# Mother_board_main.net
KiCad netlist of a schematic drawn in Altium Designer
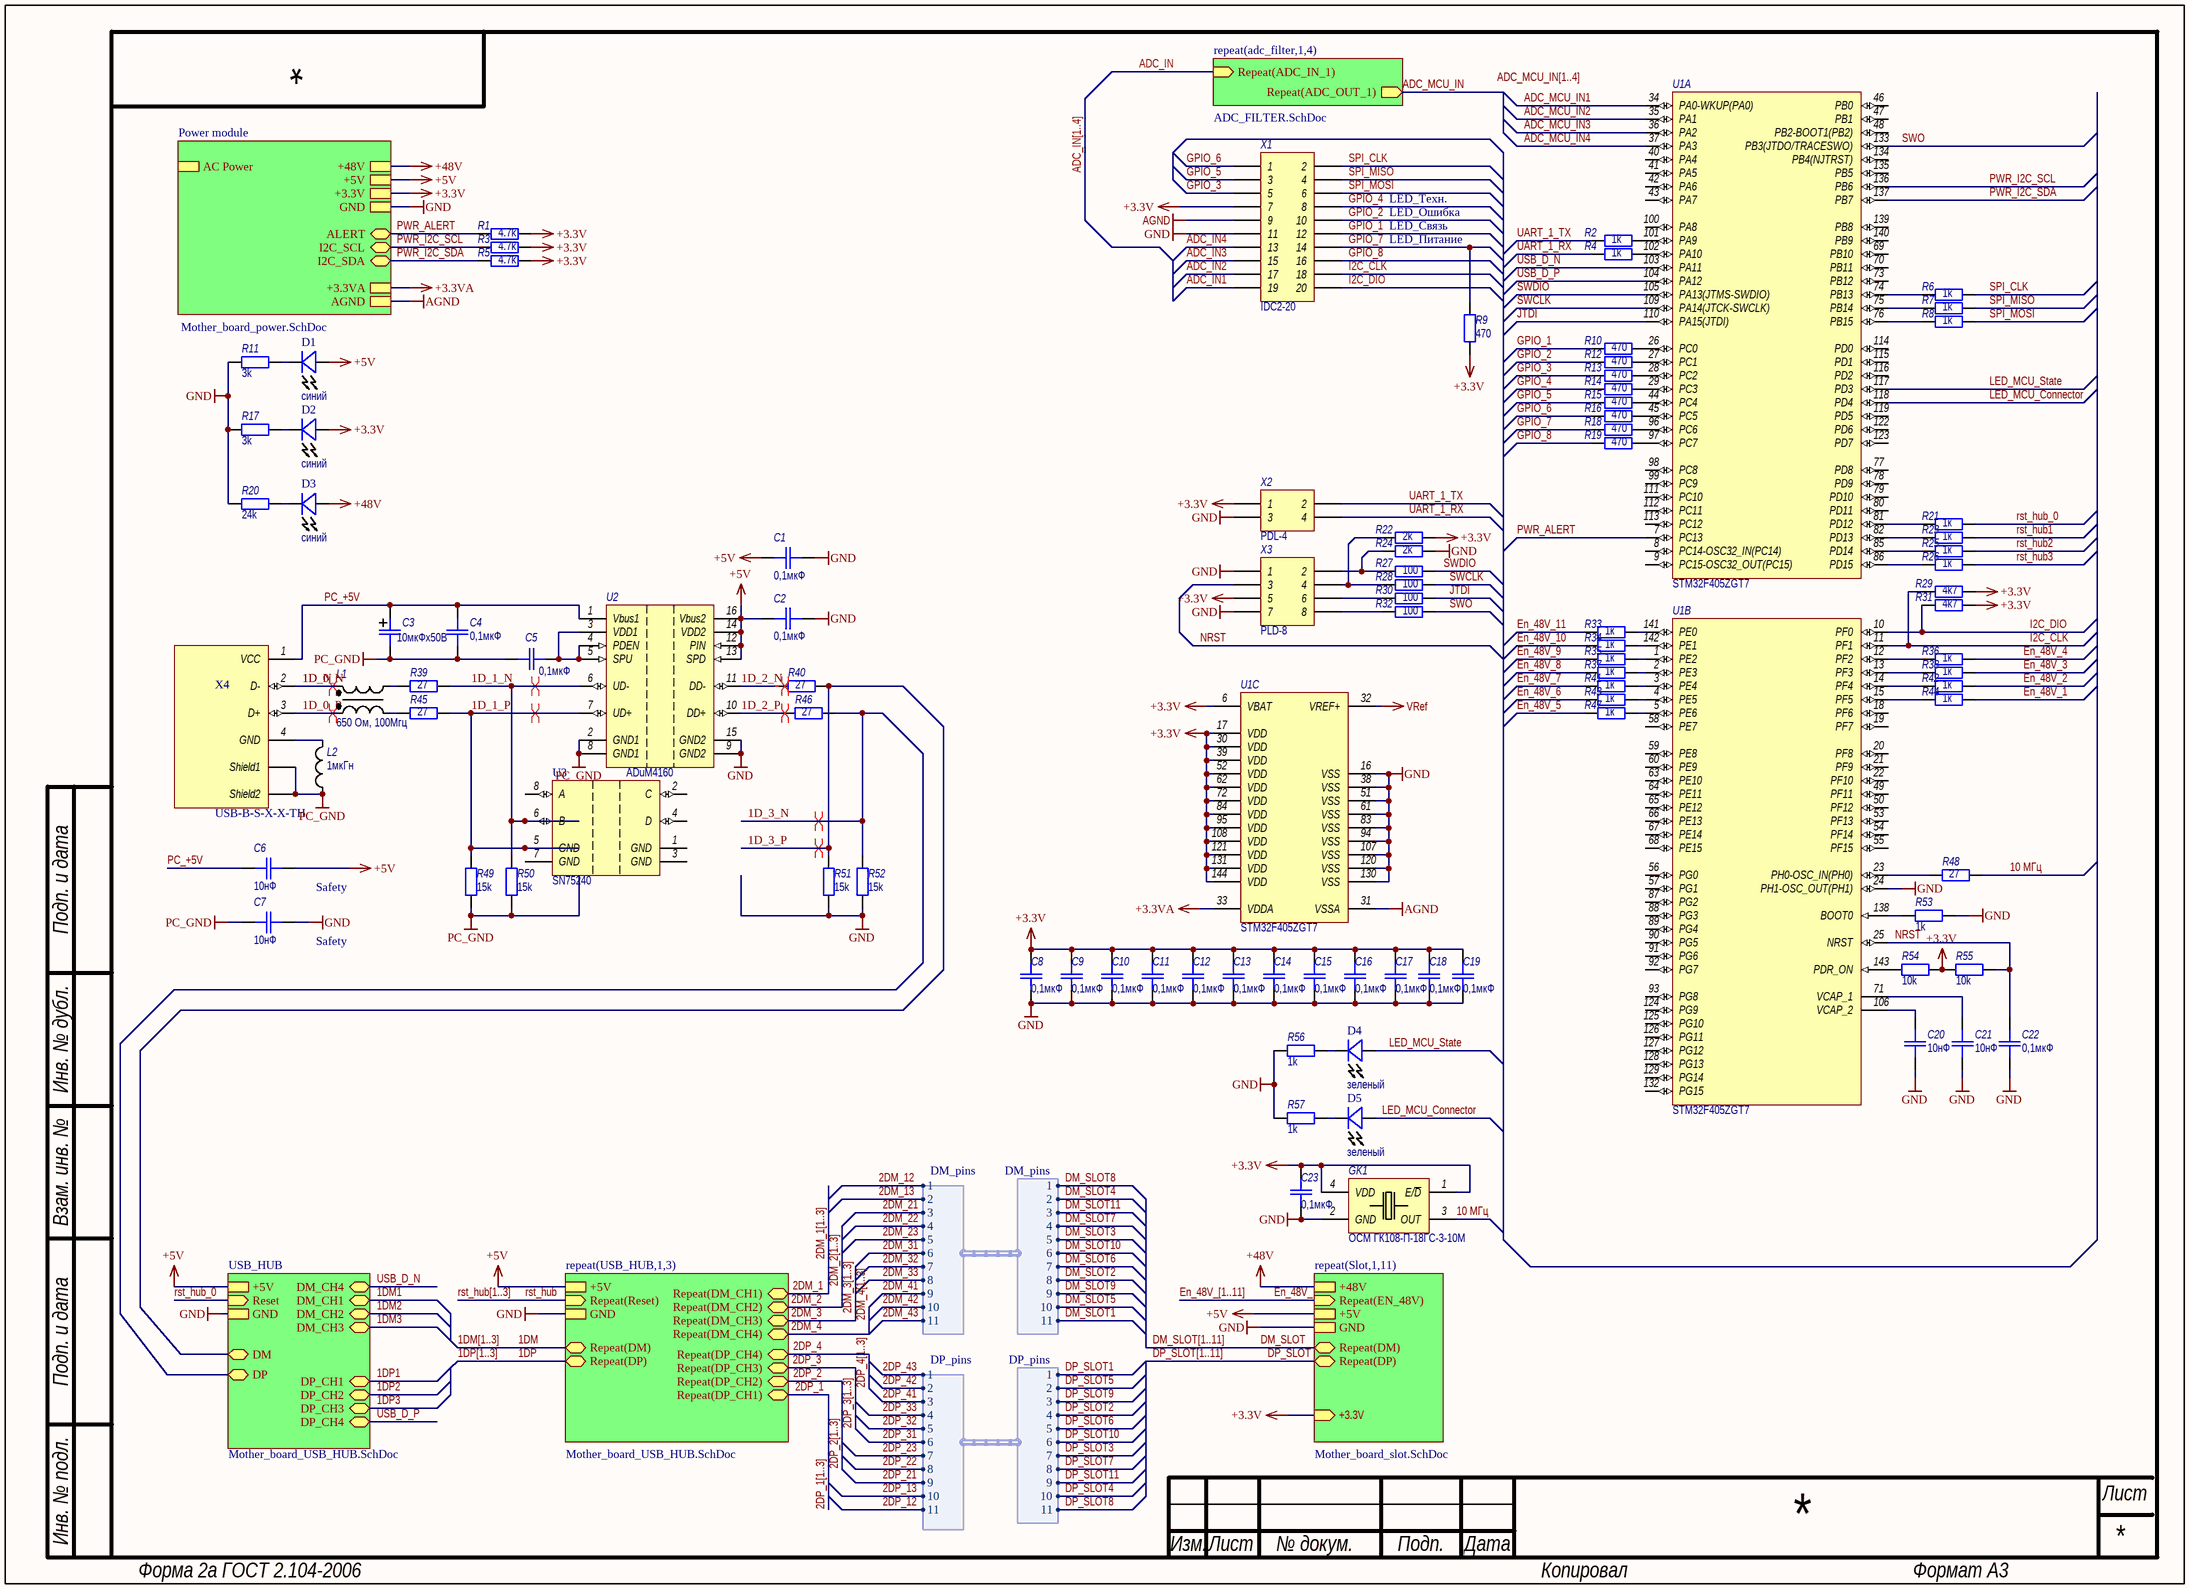
[diagram p0: Mother_board_main.SchDoc]

(export (version "E")
  (design (tool "Eeschema 10.0.6"))
  (components
    (comp (ref "C1")
      (value "0,1мкФ")
      (footprint "SMD_0805")
      (description "Capacitor")
      (libsource (lib "Passive") (part "Capacitor"))
    )
    (comp (ref "C2")
      (value "0,1мкФ")
      (footprint "SMD_0805")
      (description "Capacitor")
      (libsource (lib "Passive") (part "Capacitor"))
    )
    (comp (ref "C3")
      (value "10мкФх50В")
      (footprint "SMD_size_B")
      (description "Polarized capacitor")
      (libsource (lib "Passive") (part "Capacitor_pol"))
    )
    (comp (ref "C4")
      (value "0,1мкФ")
      (footprint "SMD_0805")
      (description "Capacitor")
      (libsource (lib "Passive") (part "Capacitor"))
    )
    (comp (ref "C5")
      (value "0,1мкФ")
      (footprint "SMD_0805")
      (description "Capacitor")
      (libsource (lib "Passive") (part "Capacitor"))
    )
    (comp (ref "C6")
      (value "10нФ")
      (footprint "SMD_0805")
      (description "Capacitor")
      (libsource (lib "Passive") (part "Capacitor"))
    )
    (comp (ref "C7")
      (value "10нФ")
      (footprint "SMD_0805")
      (description "Capacitor")
      (libsource (lib "Passive") (part "Capacitor"))
    )
    (comp (ref "C8")
      (value "0,1мкФ")
      (footprint "SMD_0805")
      (description "Capacitor")
      (libsource (lib "Passive") (part "Capacitor"))
    )
    (comp (ref "C9")
      (value "0,1мкФ")
      (footprint "SMD_0805")
      (description "Capacitor")
      (libsource (lib "Passive") (part "Capacitor"))
    )
    (comp (ref "C10")
      (value "0,1мкФ")
      (footprint "SMD_0805")
      (description "Capacitor")
      (libsource (lib "Passive") (part "Capacitor"))
    )
    (comp (ref "C11")
      (value "0,1мкФ")
      (footprint "SMD_0805")
      (description "Capacitor")
      (libsource (lib "Passive") (part "Capacitor"))
    )
    (comp (ref "C12")
      (value "0,1мкФ")
      (footprint "SMD_0805")
      (description "Capacitor")
      (libsource (lib "Passive") (part "Capacitor"))
    )
    (comp (ref "C13")
      (value "0,1мкФ")
      (footprint "SMD_0805")
      (description "Capacitor")
      (libsource (lib "Passive") (part "Capacitor"))
    )
    (comp (ref "C14")
      (value "0,1мкФ")
      (footprint "SMD_0805")
      (description "Capacitor")
      (libsource (lib "Passive") (part "Capacitor"))
    )
    (comp (ref "C15")
      (value "0,1мкФ")
      (footprint "SMD_0805")
      (description "Capacitor")
      (libsource (lib "Passive") (part "Capacitor"))
    )
    (comp (ref "C16")
      (value "0,1мкФ")
      (footprint "SMD_0805")
      (description "Capacitor")
      (libsource (lib "Passive") (part "Capacitor"))
    )
    (comp (ref "C17")
      (value "0,1мкФ")
      (footprint "SMD_0805")
      (description "Capacitor")
      (libsource (lib "Passive") (part "Capacitor"))
    )
    (comp (ref "C18")
      (value "0,1мкФ")
      (footprint "SMD_0805")
      (description "Capacitor")
      (libsource (lib "Passive") (part "Capacitor"))
    )
    (comp (ref "C19")
      (value "0,1мкФ")
      (footprint "SMD_0805")
      (description "Capacitor")
      (libsource (lib "Passive") (part "Capacitor"))
    )
    (comp (ref "C20")
      (value "10нФ")
      (footprint "SMD_0805")
      (description "Capacitor")
      (libsource (lib "Passive") (part "Capacitor"))
    )
    (comp (ref "C21")
      (value "10нФ")
      (footprint "SMD_0805")
      (description "Capacitor")
      (libsource (lib "Passive") (part "Capacitor"))
    )
    (comp (ref "C22")
      (value "0,1мкФ")
      (footprint "SMD_0805")
      (description "Capacitor")
      (libsource (lib "Passive") (part "Capacitor"))
    )
    (comp (ref "C23")
      (value "0,1мкФ")
      (footprint "SMD_0805")
      (description "Capacitor")
      (libsource (lib "Passive") (part "Capacitor"))
    )
    (comp (ref "D1")
      (value "синий")
      (footprint "LED-0805")
      (fields (field (name "Comment") "LED"))
      (libsource (lib "*") (part "LED"))
    )
    (comp (ref "D2")
      (value "синий")
      (footprint "LED-0805")
      (fields (field (name "Comment") "LED"))
      (libsource (lib "*") (part "LED"))
    )
    (comp (ref "D3")
      (value "синий")
      (footprint "LED-0805")
      (fields (field (name "Comment") "LED"))
      (libsource (lib "*") (part "LED"))
    )
    (comp (ref "D4")
      (value "зеленый")
      (footprint "LED-0805+circle")
      (fields (field (name "Comment") "LED"))
      (libsource (lib "Diod") (part "LED"))
    )
    (comp (ref "D5")
      (value "зеленый")
      (footprint "LED-0805+circle")
      (fields (field (name "Comment") "LED"))
      (libsource (lib "Diod") (part "LED"))
    )
    (comp (ref "GK1")
      (value "GK108-P")
      (footprint "SMD_7050_Crystal_Oscillator")
      (description "Crystall oscillator, CMOS, 3.3V, SMD7050")
      (fields (field (name "НАИМЕНОВАНИЕ") "ОСМ ГК108-П-18ГС-3-10М"))
      (libsource (lib "Oscillator") (part "Crystal_Oscillator"))
    )
    (comp (ref "L1")
      (value "650 Ом, 100Мгц")
      (footprint "ACM2012")
      (description "Coupled inductor")
      (libsource (lib "Passive") (part "Inductor_coupled"))
    )
    (comp (ref "L2")
      (value "1мкГн")
      (footprint "SMD_0805")
      (description "Inductor")
      (libsource (lib "Passive") (part "Inductor"))
    )
    (comp (ref "R1")
      (value "4.7k")
      (footprint "SMD_0805")
      (description "Resistor")
      (libsource (lib "*") (part "Resistor"))
    )
    (comp (ref "R2")
      (value "1k")
      (footprint "SMD_0805")
      (description "Resistor")
      (libsource (lib "") (part "Resistor_2"))
    )
    (comp (ref "R3")
      (value "4.7k")
      (footprint "SMD_0805")
      (description "Resistor")
      (libsource (lib "*") (part "Resistor"))
    )
    (comp (ref "R4")
      (value "1k")
      (footprint "SMD_0805")
      (description "Resistor")
      (libsource (lib "") (part "Resistor_2"))
    )
    (comp (ref "R5")
      (value "4.7k")
      (footprint "SMD_0805")
      (description "Resistor")
      (libsource (lib "*") (part "Resistor"))
    )
    (comp (ref "R6")
      (value "1k")
      (footprint "SMD_0805")
      (description "Resistor")
      (libsource (lib "") (part "Resistor_2"))
    )
    (comp (ref "R7")
      (value "1k")
      (footprint "SMD_0805")
      (description "Resistor")
      (libsource (lib "") (part "Resistor_2"))
    )
    (comp (ref "R8")
      (value "1k")
      (footprint "SMD_0805")
      (description "Resistor")
      (libsource (lib "") (part "Resistor_2"))
    )
    (comp (ref "R9")
      (value "470")
      (footprint "SMD_0805")
      (description "Resistor")
      (libsource (lib "") (part "Resistor_1"))
    )
    (comp (ref "R10")
      (value "470")
      (footprint "SMD_0805")
      (description "Resistor")
      (libsource (lib "") (part "Resistor_2"))
    )
    (comp (ref "R11")
      (value "3k")
      (footprint "SMD_0805")
      (description "Resistor")
      (libsource (lib "") (part "Resistor_2"))
    )
    (comp (ref "R12")
      (value "470")
      (footprint "SMD_0805")
      (description "Resistor")
      (libsource (lib "") (part "Resistor_2"))
    )
    (comp (ref "R13")
      (value "470")
      (footprint "SMD_0805")
      (description "Resistor")
      (libsource (lib "") (part "Resistor_2"))
    )
    (comp (ref "R14")
      (value "470")
      (footprint "SMD_0805")
      (description "Resistor")
      (libsource (lib "") (part "Resistor_2"))
    )
    (comp (ref "R15")
      (value "470")
      (footprint "SMD_0805")
      (description "Resistor")
      (libsource (lib "") (part "Resistor_2"))
    )
    (comp (ref "R16")
      (value "470")
      (footprint "SMD_0805")
      (description "Resistor")
      (libsource (lib "") (part "Resistor_2"))
    )
    (comp (ref "R17")
      (value "3k")
      (footprint "SMD_0805")
      (description "Resistor")
      (libsource (lib "") (part "Resistor_2"))
    )
    (comp (ref "R18")
      (value "470")
      (footprint "SMD_0805")
      (description "Resistor")
      (libsource (lib "") (part "Resistor_2"))
    )
    (comp (ref "R19")
      (value "470")
      (footprint "SMD_0805")
      (description "Resistor")
      (libsource (lib "") (part "Resistor_2"))
    )
    (comp (ref "R20")
      (value "24k")
      (footprint "SMD_0805")
      (description "Resistor")
      (libsource (lib "") (part "Resistor_2"))
    )
    (comp (ref "R21")
      (value "1к")
      (footprint "SMD_0805")
      (description "Resistor")
      (libsource (lib "Passive") (part "Resistor"))
    )
    (comp (ref "R22")
      (value "2k")
      (footprint "SMD_0805")
      (description "Resistor")
      (libsource (lib "") (part "Resistor_2"))
    )
    (comp (ref "R23")
      (value "1к")
      (footprint "SMD_0805")
      (description "Resistor")
      (libsource (lib "Passive") (part "Resistor"))
    )
    (comp (ref "R24")
      (value "2k")
      (footprint "SMD_0805")
      (description "Resistor")
      (libsource (lib "") (part "Resistor_2"))
    )
    (comp (ref "R25")
      (value "1к")
      (footprint "SMD_0805")
      (description "Resistor")
      (libsource (lib "Passive") (part "Resistor"))
    )
    (comp (ref "R26")
      (value "1к")
      (footprint "SMD_0805")
      (description "Resistor")
      (libsource (lib "Passive") (part "Resistor"))
    )
    (comp (ref "R27")
      (value "100")
      (footprint "SMD_0805")
      (description "Resistor")
      (libsource (lib "") (part "Resistor_2"))
    )
    (comp (ref "R28")
      (value "100")
      (footprint "SMD_0805")
      (description "Resistor")
      (libsource (lib "") (part "Resistor_2"))
    )
    (comp (ref "R29")
      (value "4k7")
      (footprint "SMD_0805")
      (description "Resistor")
      (libsource (lib "") (part "Resistor_2"))
    )
    (comp (ref "R30")
      (value "100")
      (footprint "SMD_0805")
      (description "Resistor")
      (libsource (lib "") (part "Resistor_2"))
    )
    (comp (ref "R31")
      (value "4k7")
      (footprint "SMD_0805")
      (description "Resistor")
      (libsource (lib "") (part "Resistor_2"))
    )
    (comp (ref "R32")
      (value "100")
      (footprint "SMD_0805")
      (description "Resistor")
      (libsource (lib "") (part "Resistor_2"))
    )
    (comp (ref "R33")
      (value "1к")
      (footprint "SMD_0805")
      (description "Resistor")
      (libsource (lib "Passive") (part "Resistor"))
    )
    (comp (ref "R34")
      (value "1к")
      (footprint "SMD_0805")
      (description "Resistor")
      (libsource (lib "Passive") (part "Resistor"))
    )
    (comp (ref "R35")
      (value "1к")
      (footprint "SMD_0805")
      (description "Resistor")
      (libsource (lib "Passive") (part "Resistor"))
    )
    (comp (ref "R36")
      (value "1к")
      (footprint "SMD_0805")
      (description "Resistor")
      (libsource (lib "Passive") (part "Resistor"))
    )
    (comp (ref "R37")
      (value "1к")
      (footprint "SMD_0805")
      (description "Resistor")
      (libsource (lib "Passive") (part "Resistor"))
    )
    (comp (ref "R38")
      (value "1к")
      (footprint "SMD_0805")
      (description "Resistor")
      (libsource (lib "Passive") (part "Resistor"))
    )
    (comp (ref "R39")
      (value "27")
      (footprint "SMD_0805")
      (description "Resistor")
      (libsource (lib "") (part "Resistor_1"))
    )
    (comp (ref "R40")
      (value "27")
      (footprint "SMD_0805")
      (description "Resistor")
      (libsource (lib "") (part "Resistor_1"))
    )
    (comp (ref "R41")
      (value "1к")
      (footprint "SMD_0805")
      (description "Resistor")
      (libsource (lib "Passive") (part "Resistor"))
    )
    (comp (ref "R42")
      (value "1к")
      (footprint "SMD_0805")
      (description "Resistor")
      (libsource (lib "Passive") (part "Resistor"))
    )
    (comp (ref "R43")
      (value "1к")
      (footprint "SMD_0805")
      (description "Resistor")
      (libsource (lib "Passive") (part "Resistor"))
    )
    (comp (ref "R44")
      (value "1к")
      (footprint "SMD_0805")
      (description "Resistor")
      (libsource (lib "Passive") (part "Resistor"))
    )
    (comp (ref "R45")
      (value "27")
      (footprint "SMD_0805")
      (description "Resistor")
      (libsource (lib "") (part "Resistor_1"))
    )
    (comp (ref "R46")
      (value "27")
      (footprint "SMD_0805")
      (description "Resistor")
      (libsource (lib "") (part "Resistor_1"))
    )
    (comp (ref "R47")
      (value "1к")
      (footprint "SMD_0805")
      (description "Resistor")
      (libsource (lib "Passive") (part "Resistor"))
    )
    (comp (ref "R48")
      (value "27")
      (footprint "SMD_0805")
      (description "Resistor")
      (libsource (lib "Passive") (part "Resistor"))
    )
    (comp (ref "R49")
      (value "15k")
      (footprint "SMD_0805")
      (description "Resistor")
      (libsource (lib "") (part "Resistor_3"))
    )
    (comp (ref "R50")
      (value "15k")
      (footprint "SMD_0805")
      (description "Resistor")
      (libsource (lib "") (part "Resistor_3"))
    )
    (comp (ref "R51")
      (value "15k")
      (footprint "SMD_0805")
      (description "Resistor")
      (libsource (lib "") (part "Resistor_2"))
    )
    (comp (ref "R52")
      (value "15k")
      (footprint "SMD_0805")
      (description "Resistor")
      (libsource (lib "") (part "Resistor_2"))
    )
    (comp (ref "R53")
      (value "1k")
      (footprint "SMD_0805")
      (description "Resistor")
      (libsource (lib "Passive") (part "Resistor"))
    )
    (comp (ref "R54")
      (value "10k")
      (footprint "SMD_0805")
      (description "Resistor")
      (libsource (lib "Passive") (part "Resistor"))
    )
    (comp (ref "R55")
      (value "10k")
      (footprint "SMD_0805")
      (description "Resistor")
      (libsource (lib "Passive") (part "Resistor"))
    )
    (comp (ref "R56")
      (value "1k")
      (footprint "SMD_0805")
      (description "Resistor")
      (libsource (lib "") (part "Resistor_2"))
    )
    (comp (ref "R57")
      (value "1k")
      (footprint "SMD_0805")
      (description "Resistor")
      (libsource (lib "") (part "Resistor_2"))
    )
    (comp (ref "U1")
      (value "STM32F405ZGT7")
      (footprint "LQFP144")
      (fields (field (name "НАИМЕНОВАНИЕ") "STM32F405ZGT7"))
      (libsource (lib "MCU") (part "STM32F405ZGT"))
    )
    (comp (ref "U2")
      (value "ADuM1402")
      (footprint "SOIC-16-WIDE")
      (description "Quad Channel Digital Isolator, 2.5 KV rms Insulation Rating")
      (fields (field (name "НАИМЕНОВАНИЕ") "ADuM4160"))
      (libsource (lib "Isolator") (part "ADuM4160"))
    )
    (comp (ref "U3")
      (value "SN75240")
      (footprint "SN75240")
      (description "ESD-защита")
      (fields (field (name "НАИМЕНОВАНИЕ") "SN75240"))
      (libsource (lib "SN75240") (part "SN75240"))
    )
    (comp (ref "X1")
      (value "Header 2X20")
      (footprint "PLD2-20")
      (description "Header, 20-Pin, Dual row")
      (fields (field (name "НАИМЕНОВАНИЕ") "IDC2-20"))
      (libsource (lib "Connector") (part "Header 2X20"))
    )
    (comp (ref "X2")
      (value "Header 2X4")
      (footprint "PBD-4")
      (description "Header, 4-Pin, Dual row")
      (fields (field (name "НАИМЕНОВАНИЕ") "PDL-4"))
      (libsource (lib "Connector") (part "Header 2X4"))
    )
    (comp (ref "X3")
      (value "Header 2X8")
      (footprint "PBD-8")
      (description "Header, 8-Pin, Dual row")
      (fields (field (name "НАИМЕНОВАНИЕ") "PLD-8"))
      (libsource (lib "Connector") (part "Header 2X8"))
    )
    (comp (ref "X4")
      (value "USB-B-S-X-X-TH")
      (footprint "*SAMTEC_USB-B-S-X-X-TH_USB-B-S-X-X-TH(Primary)")
      (description "USB-B (USB TYPE-B) USB 2.0 Receptacle Connector 4 Position Through Hole, Right Angle")
      (fields
        (field (name "BUYPART") "https://www.snapeda.com/parts/USB-B-S-F-B-TH/Samtec%20Inc./view-part/226211/?ref=eda")
        (field (name "MP") "USB-B-S-F-B-TH")
      )
      (libsource (lib "USB-B-S-X-X-TH") (part "USB-B-S-X-X-TH"))
    )
  )
  (nets
    (net (code "5") (name "+3.3V") (class "Default")
      (node (ref "C10") (pin "2") (pinfunction "2_2") (pintype "passive"))
      (node (ref "C11") (pin "2") (pinfunction "2_2") (pintype "passive"))
      (node (ref "C12") (pin "2") (pinfunction "2_2") (pintype "passive"))
      (node (ref "C13") (pin "2") (pinfunction "2_2") (pintype "passive"))
      (node (ref "C14") (pin "2") (pinfunction "2_2") (pintype "passive"))
      (node (ref "C15") (pin "2") (pinfunction "2_2") (pintype "passive"))
      (node (ref "C16") (pin "2") (pinfunction "2_2") (pintype "passive"))
      (node (ref "C17") (pin "2") (pinfunction "2_2") (pintype "passive"))
      (node (ref "C18") (pin "2") (pinfunction "2_2") (pintype "passive"))
      (node (ref "C19") (pin "2") (pinfunction "2_2") (pintype "passive"))
      (node (ref "C23") (pin "2") (pinfunction "2_2") (pintype "passive"))
      (node (ref "C8") (pin "2") (pinfunction "2_2") (pintype "passive"))
      (node (ref "C9") (pin "2") (pinfunction "2_2") (pintype "passive"))
      (node (ref "D2") (pin "1") (pinfunction "A_1") (pintype "passive"))
      (node (ref "GK1") (pin "1") (pinfunction "E/~{D}_1") (pintype "passive"))
      (node (ref "GK1") (pin "4") (pinfunction "VDD_4") (pintype "passive"))
      (node (ref "R1") (pin "1") (pinfunction "1_1") (pintype "passive"))
      (node (ref "R22") (pin "2") (pinfunction "2_2") (pintype "passive"))
      (node (ref "R29") (pin "2") (pinfunction "2_2") (pintype "passive"))
      (node (ref "R3") (pin "1") (pinfunction "1_1") (pintype "passive"))
      (node (ref "R31") (pin "2") (pinfunction "2_2") (pintype "passive"))
      (node (ref "R5") (pin "1") (pinfunction "1_1") (pintype "passive"))
      (node (ref "R54") (pin "1") (pinfunction "1_1") (pintype "passive"))
      (node (ref "R55") (pin "2") (pinfunction "2_2") (pintype "passive"))
      (node (ref "R9") (pin "1") (pinfunction "1_1") (pintype "passive"))
      (node (ref "U1") (pin "108") (pinfunction "VDD_108") (pintype "power_in"))
      (node (ref "U1") (pin "121") (pinfunction "VDD_121") (pintype "power_in"))
      (node (ref "U1") (pin "131") (pinfunction "VDD_131") (pintype "power_in"))
      (node (ref "U1") (pin "144") (pinfunction "VDD_144") (pintype "power_in"))
      (node (ref "U1") (pin "17") (pinfunction "VDD_17") (pintype "power_in"))
      (node (ref "U1") (pin "30") (pinfunction "VDD_30") (pintype "power_in"))
      (node (ref "U1") (pin "39") (pinfunction "VDD_39") (pintype "power_in"))
      (node (ref "U1") (pin "52") (pinfunction "VDD_52") (pintype "power_in"))
      (node (ref "U1") (pin "6") (pinfunction "VBAT_6") (pintype "power_in"))
      (node (ref "U1") (pin "62") (pinfunction "VDD_62") (pintype "power_in"))
      (node (ref "U1") (pin "72") (pinfunction "VDD_72") (pintype "power_in"))
      (node (ref "U1") (pin "84") (pinfunction "VDD_84") (pintype "power_in"))
      (node (ref "U1") (pin "95") (pinfunction "VDD_95") (pintype "power_in"))
      (node (ref "X1") (pin "7") (pinfunction "7_7") (pintype "passive"))
      (node (ref "X2") (pin "1") (pinfunction "1_1") (pintype "passive"))
      (node (ref "X3") (pin "5") (pinfunction "5_5") (pintype "passive"))
    )
    (net (code "6") (name "+3.3VA") (class "Default")
      (node (ref "U1") (pin "33") (pinfunction "VDDA_33") (pintype "power_in"))
    )
    (net (code "7") (name "+5V") (class "Default")
      (node (ref "C1") (pin "2") (pinfunction "2_2") (pintype "passive"))
      (node (ref "C2") (pin "2") (pinfunction "2_2") (pintype "passive"))
      (node (ref "C6") (pin "2") (pinfunction "2_2") (pintype "passive"))
      (node (ref "D1") (pin "1") (pinfunction "A_1") (pintype "passive"))
      (node (ref "U2") (pin "12") (pinfunction "PIN_12") (pintype "input"))
      (node (ref "U2") (pin "13") (pinfunction "SPD_13") (pintype "input"))
      (node (ref "U2") (pin "14") (pinfunction "VDD2_14") (pintype "power_in"))
      (node (ref "U2") (pin "16") (pinfunction "Vbus2_16") (pintype "power_in"))
    )
    (net (code "8") (name "+48V") (class "Default")
      (node (ref "D3") (pin "1") (pinfunction "A_1") (pintype "passive"))
    )
    (net (code "19") (name "/1D_0_N") (class "Default")
      (node (ref "L1") (pin "2") (pinfunction "2_2") (pintype "passive"))
      (node (ref "X4") (pin "2") (pinfunction "D-_2") (pintype "bidirectional"))
    )
    (net (code "20") (name "/1D_0_P") (class "Default")
      (node (ref "L1") (pin "3") (pinfunction "3_3") (pintype "passive"))
      (node (ref "X4") (pin "3") (pinfunction "D+_3") (pintype "bidirectional"))
    )
    (net (code "21") (name "/1D_1_N") (class "Default")
      (node (ref "R39") (pin "2") (pinfunction "2_2") (pintype "passive"))
      (node (ref "R50") (pin "2") (pinfunction "2_2") (pintype "passive"))
      (node (ref "U2") (pin "6") (pinfunction "UD-_6") (pintype "bidirectional"))
      (node (ref "U3") (pin "6") (pinfunction "B_6") (pintype "bidirectional"))
    )
    (net (code "22") (name "/1D_1_P") (class "Default")
      (node (ref "R45") (pin "2") (pinfunction "2_2") (pintype "passive"))
      (node (ref "R49") (pin "2") (pinfunction "2_2") (pintype "passive"))
      (node (ref "U2") (pin "7") (pinfunction "UD+_7") (pintype "bidirectional"))
      (node (ref "U3") (pin "5") (pinfunction "GND_5") (pintype "power_in"))
    )
    (net (code "23") (name "/1D_2_N") (class "Default")
      (node (ref "R40") (pin "1") (pinfunction "1_1") (pintype "passive"))
      (node (ref "U2") (pin "11") (pinfunction "DD-_11") (pintype "bidirectional"))
    )
    (net (code "24") (name "/1D_2_P") (class "Default")
      (node (ref "R46") (pin "1") (pinfunction "1_1") (pintype "passive"))
      (node (ref "U2") (pin "10") (pinfunction "DD+_10") (pintype "bidirectional"))
    )
    (net (code "25") (name "/1D_3_N") (class "Default")
      (node (ref "R46") (pin "2") (pinfunction "2_2") (pintype "passive"))
      (node (ref "R52") (pin "1") (pinfunction "1_1") (pintype "passive"))
    )
    (net (code "26") (name "/1D_3_P") (class "Default")
      (node (ref "R40") (pin "2") (pinfunction "2_2") (pintype "passive"))
      (node (ref "R51") (pin "1") (pinfunction "1_1") (pintype "passive"))
    )
    (net (code "65") (name "/10 МГц") (class "Default")
      (node (ref "GK1") (pin "3") (pinfunction "OUT_3") (pintype "passive"))
      (node (ref "R48") (pin "1") (pinfunction "1_1") (pintype "passive"))
    )
    (net (code "68") (name "/ADC_IN1") (class "Default")
      (node (ref "X1") (pin "19") (pinfunction "19_19") (pintype "passive"))
    )
    (net (code "69") (name "/ADC_IN2") (class "Default")
      (node (ref "X1") (pin "17") (pinfunction "17_17") (pintype "passive"))
    )
    (net (code "70") (name "/ADC_IN3") (class "Default")
      (node (ref "X1") (pin "15") (pinfunction "15_15") (pintype "passive"))
    )
    (net (code "71") (name "/ADC_IN4") (class "Default")
      (node (ref "X1") (pin "13") (pinfunction "13_13") (pintype "passive"))
    )
    (net (code "74") (name "/ADC_MCU_IN1") (class "Default")
      (node (ref "U1") (pin "34") (pinfunction "PA0-WKUP(PA0)_34") (pintype "bidirectional"))
    )
    (net (code "75") (name "/ADC_MCU_IN2") (class "Default")
      (node (ref "U1") (pin "35") (pinfunction "PA1_35") (pintype "bidirectional"))
    )
    (net (code "76") (name "/ADC_MCU_IN3") (class "Default")
      (node (ref "U1") (pin "36") (pinfunction "PA2_36") (pintype "bidirectional"))
    )
    (net (code "77") (name "/ADC_MCU_IN4") (class "Default")
      (node (ref "U1") (pin "37") (pinfunction "PA3_37") (pintype "bidirectional"))
    )
    (net (code "106") (name "/En_48V_1") (class "Default")
      (node (ref "R44") (pin "1") (pinfunction "1_1") (pintype "passive"))
    )
    (net (code "107") (name "/En_48V_2") (class "Default")
      (node (ref "R42") (pin "1") (pinfunction "1_1") (pintype "passive"))
    )
    (net (code "108") (name "/En_48V_3") (class "Default")
      (node (ref "R38") (pin "1") (pinfunction "1_1") (pintype "passive"))
    )
    (net (code "109") (name "/En_48V_4") (class "Default")
      (node (ref "R36") (pin "1") (pinfunction "1_1") (pintype "passive"))
    )
    (net (code "110") (name "/En_48V_5") (class "Default")
      (node (ref "R47") (pin "2") (pinfunction "2_2") (pintype "passive"))
    )
    (net (code "111") (name "/En_48V_6") (class "Default")
      (node (ref "R43") (pin "2") (pinfunction "2_2") (pintype "passive"))
    )
    (net (code "112") (name "/En_48V_7") (class "Default")
      (node (ref "R41") (pin "2") (pinfunction "2_2") (pintype "passive"))
    )
    (net (code "113") (name "/En_48V_8") (class "Default")
      (node (ref "R37") (pin "2") (pinfunction "2_2") (pintype "passive"))
    )
    (net (code "114") (name "/En_48V_9") (class "Default")
      (node (ref "R35") (pin "2") (pinfunction "2_2") (pintype "passive"))
    )
    (net (code "115") (name "/En_48V_10") (class "Default")
      (node (ref "R34") (pin "2") (pinfunction "2_2") (pintype "passive"))
    )
    (net (code "116") (name "/En_48V_11") (class "Default")
      (node (ref "R33") (pin "2") (pinfunction "2_2") (pintype "passive"))
    )
    (net (code "117") (name "/GPIO_1") (class "Default")
      (node (ref "R10") (pin "1") (pinfunction "1_1") (pintype "passive"))
      (node (ref "X1") (pin "12") (pinfunction "12_12") (pintype "passive"))
    )
    (net (code "118") (name "/GPIO_2") (class "Default")
      (node (ref "R12") (pin "1") (pinfunction "1_1") (pintype "passive"))
      (node (ref "X1") (pin "10") (pinfunction "10_10") (pintype "passive"))
    )
    (net (code "119") (name "/GPIO_3") (class "Default")
      (node (ref "R13") (pin "1") (pinfunction "1_1") (pintype "passive"))
      (node (ref "X1") (pin "5") (pinfunction "5_5") (pintype "passive"))
    )
    (net (code "120") (name "/GPIO_4") (class "Default")
      (node (ref "R14") (pin "1") (pinfunction "1_1") (pintype "passive"))
      (node (ref "X1") (pin "8") (pinfunction "8_8") (pintype "passive"))
    )
    (net (code "121") (name "/GPIO_5") (class "Default")
      (node (ref "R15") (pin "1") (pinfunction "1_1") (pintype "passive"))
      (node (ref "X1") (pin "3") (pinfunction "3_3") (pintype "passive"))
    )
    (net (code "122") (name "/GPIO_6") (class "Default")
      (node (ref "R16") (pin "1") (pinfunction "1_1") (pintype "passive"))
      (node (ref "X1") (pin "1") (pinfunction "1_1") (pintype "passive"))
    )
    (net (code "123") (name "/GPIO_7") (class "Default")
      (node (ref "R18") (pin "1") (pinfunction "1_1") (pintype "passive"))
      (node (ref "R9") (pin "2") (pinfunction "2_2") (pintype "passive"))
      (node (ref "X1") (pin "14") (pinfunction "14_14") (pintype "passive"))
    )
    (net (code "124") (name "/GPIO_8") (class "Default")
      (node (ref "R19") (pin "1") (pinfunction "1_1") (pintype "passive"))
      (node (ref "X1") (pin "16") (pinfunction "16_16") (pintype "passive"))
    )
    (net (code "125") (name "/I2C_CLK") (class "Default")
      (node (ref "R29") (pin "1") (pinfunction "1_1") (pintype "passive"))
      (node (ref "U1") (pin "11") (pinfunction "PF1_11") (pintype "bidirectional"))
      (node (ref "X1") (pin "18") (pinfunction "18_18") (pintype "passive"))
    )
    (net (code "126") (name "/I2C_DIO") (class "Default")
      (node (ref "R31") (pin "1") (pinfunction "1_1") (pintype "passive"))
      (node (ref "U1") (pin "10") (pinfunction "PF0_10") (pintype "bidirectional"))
      (node (ref "X1") (pin "20") (pinfunction "20_20") (pintype "passive"))
    )
    (net (code "127") (name "/JTDI") (class "Default")
      (node (ref "R30") (pin "2") (pinfunction "2_2") (pintype "passive"))
      (node (ref "U1") (pin "110") (pinfunction "PA15(JTDI)_110") (pintype "bidirectional"))
    )
    (net (code "128") (name "/LED_MCU_Connector") (class "Default")
      (node (ref "D5") (pin "1") (pinfunction "A_1") (pintype "passive"))
      (node (ref "U1") (pin "118") (pinfunction "PD4_118") (pintype "bidirectional"))
    )
    (net (code "129") (name "/LED_MCU_State") (class "Default")
      (node (ref "D4") (pin "1") (pinfunction "A_1") (pintype "passive"))
      (node (ref "U1") (pin "117") (pinfunction "PD3_117") (pintype "bidirectional"))
    )
    (net (code "130") (name "/NRST") (class "Default")
      (node (ref "C22") (pin "2") (pinfunction "2_2") (pintype "passive"))
      (node (ref "R55") (pin "1") (pinfunction "1_1") (pintype "passive"))
      (node (ref "U1") (pin "25") (pinfunction "NRST_25") (pintype "bidirectional"))
      (node (ref "X3") (pin "3") (pinfunction "3_3") (pintype "passive"))
    )
    (net (code "131") (name "/PC_+5V") (class "Default")
      (node (ref "C3") (pin "1") (pinfunction "1_1") (pintype "passive"))
      (node (ref "C4") (pin "1") (pinfunction "1_1") (pintype "passive"))
      (node (ref "C6") (pin "1") (pinfunction "1_1") (pintype "passive"))
      (node (ref "U2") (pin "1") (pinfunction "Vbus1_1") (pintype "power_in"))
      (node (ref "X4") (pin "1") (pinfunction "VCC_1") (pintype "power_in"))
    )
    (net (code "132") (name "/PWR_ALERT") (class "Default")
      (node (ref "R1") (pin "2") (pinfunction "2_2") (pintype "passive"))
      (node (ref "U1") (pin "7") (pinfunction "PC13_7") (pintype "bidirectional"))
    )
    (net (code "133") (name "/PWR_I2C_SCL") (class "Default")
      (node (ref "R3") (pin "2") (pinfunction "2_2") (pintype "passive"))
      (node (ref "U1") (pin "136") (pinfunction "PB6_136") (pintype "bidirectional"))
    )
    (net (code "134") (name "/PWR_I2C_SDA") (class "Default")
      (node (ref "R5") (pin "2") (pinfunction "2_2") (pintype "passive"))
      (node (ref "U1") (pin "137") (pinfunction "PB7_137") (pintype "bidirectional"))
    )
    (net (code "135") (name "/SPI_CLK") (class "Default")
      (node (ref "R6") (pin "2") (pinfunction "2_2") (pintype "passive"))
      (node (ref "X1") (pin "2") (pinfunction "2_2") (pintype "passive"))
    )
    (net (code "136") (name "/SPI_MISO") (class "Default")
      (node (ref "R7") (pin "2") (pinfunction "2_2") (pintype "passive"))
      (node (ref "X1") (pin "4") (pinfunction "4_4") (pintype "passive"))
    )
    (net (code "137") (name "/SPI_MOSI") (class "Default")
      (node (ref "R8") (pin "2") (pinfunction "2_2") (pintype "passive"))
      (node (ref "X1") (pin "6") (pinfunction "6_6") (pintype "passive"))
    )
    (net (code "138") (name "/SWCLK") (class "Default")
      (node (ref "R28") (pin "2") (pinfunction "2_2") (pintype "passive"))
      (node (ref "U1") (pin "109") (pinfunction "PA14(JTCK-SWCLK)_109") (pintype "bidirectional"))
    )
    (net (code "139") (name "/SWDIO") (class "Default")
      (node (ref "R27") (pin "2") (pinfunction "2_2") (pintype "passive"))
      (node (ref "U1") (pin "105") (pinfunction "PA13(JTMS-SWDIO)_105") (pintype "bidirectional"))
    )
    (net (code "140") (name "/SWO") (class "Default")
      (node (ref "R32") (pin "2") (pinfunction "2_2") (pintype "passive"))
      (node (ref "U1") (pin "133") (pinfunction "PB3(JTDO/TRACESWO)_133") (pintype "bidirectional"))
    )
    (net (code "141") (name "/UART_1_RX") (class "Default")
      (node (ref "R4") (pin "1") (pinfunction "1_1") (pintype "passive"))
      (node (ref "X2") (pin "4") (pinfunction "4_4") (pintype "passive"))
    )
    (net (code "142") (name "/UART_1_TX") (class "Default")
      (node (ref "R2") (pin "1") (pinfunction "1_1") (pintype "passive"))
      (node (ref "X2") (pin "2") (pinfunction "2_2") (pintype "passive"))
    )
    (net (code "143") (name "/USB_D_N") (class "Default")
      (node (ref "U1") (pin "103") (pinfunction "PA11_103") (pintype "bidirectional"))
    )
    (net (code "144") (name "/USB_D_P") (class "Default")
      (node (ref "U1") (pin "104") (pinfunction "PA12_104") (pintype "bidirectional"))
    )
    (net (code "146") (name "/rst_hub1") (class "Default")
      (node (ref "R23") (pin "1") (pinfunction "1_1") (pintype "passive"))
    )
    (net (code "147") (name "/rst_hub2") (class "Default")
      (node (ref "R25") (pin "1") (pinfunction "1_1") (pintype "passive"))
    )
    (net (code "148") (name "/rst_hub3") (class "Default")
      (node (ref "R26") (pin "1") (pinfunction "1_1") (pintype "passive"))
    )
    (net (code "150") (name "/rst_hub_0") (class "Default")
      (node (ref "R21") (pin "1") (pinfunction "1_1") (pintype "passive"))
    )
    (net (code "153") (name "AGND") (class "Default")
      (node (ref "U1") (pin "31") (pinfunction "VSSA_31") (pintype "power_in"))
      (node (ref "X1") (pin "9") (pinfunction "9_9") (pintype "passive"))
    )
    (net (code "154") (name "GND") (class "Default")
      (node (ref "C1") (pin "1") (pinfunction "1_1") (pintype "passive"))
      (node (ref "C10") (pin "1") (pinfunction "1_1") (pintype "passive"))
      (node (ref "C11") (pin "1") (pinfunction "1_1") (pintype "passive"))
      (node (ref "C12") (pin "1") (pinfunction "1_1") (pintype "passive"))
      (node (ref "C13") (pin "1") (pinfunction "1_1") (pintype "passive"))
      (node (ref "C14") (pin "1") (pinfunction "1_1") (pintype "passive"))
      (node (ref "C15") (pin "1") (pinfunction "1_1") (pintype "passive"))
      (node (ref "C16") (pin "1") (pinfunction "1_1") (pintype "passive"))
      (node (ref "C17") (pin "1") (pinfunction "1_1") (pintype "passive"))
      (node (ref "C18") (pin "1") (pinfunction "1_1") (pintype "passive"))
      (node (ref "C19") (pin "1") (pinfunction "1_1") (pintype "passive"))
      (node (ref "C2") (pin "1") (pinfunction "1_1") (pintype "passive"))
      (node (ref "C20") (pin "1") (pinfunction "1_1") (pintype "passive"))
      (node (ref "C21") (pin "1") (pinfunction "1_1") (pintype "passive"))
      (node (ref "C22") (pin "1") (pinfunction "1_1") (pintype "passive"))
      (node (ref "C23") (pin "1") (pinfunction "1_1") (pintype "passive"))
      (node (ref "C7") (pin "2") (pinfunction "2_2") (pintype "passive"))
      (node (ref "C8") (pin "1") (pinfunction "1_1") (pintype "passive"))
      (node (ref "C9") (pin "1") (pinfunction "1_1") (pintype "passive"))
      (node (ref "GK1") (pin "2") (pinfunction "GND_2") (pintype "passive"))
      (node (ref "R11") (pin "1") (pinfunction "1_1") (pintype "passive"))
      (node (ref "R17") (pin "1") (pinfunction "1_1") (pintype "passive"))
      (node (ref "R20") (pin "1") (pinfunction "1_1") (pintype "passive"))
      (node (ref "R24") (pin "2") (pinfunction "2_2") (pintype "passive"))
      (node (ref "R51") (pin "2") (pinfunction "2_2") (pintype "passive"))
      (node (ref "R52") (pin "2") (pinfunction "2_2") (pintype "passive"))
      (node (ref "R53") (pin "1") (pinfunction "1_1") (pintype "passive"))
      (node (ref "R56") (pin "1") (pinfunction "1_1") (pintype "passive"))
      (node (ref "R57") (pin "1") (pinfunction "1_1") (pintype "passive"))
      (node (ref "U1") (pin "107") (pinfunction "VSS_107") (pintype "power_in"))
      (node (ref "U1") (pin "120") (pinfunction "VSS_120") (pintype "power_in"))
      (node (ref "U1") (pin "130") (pinfunction "VSS_130") (pintype "power_in"))
      (node (ref "U1") (pin "16") (pinfunction "VSS_16") (pintype "power_in"))
      (node (ref "U1") (pin "24") (pinfunction "PH1-OSC_OUT(PH1)_24") (pintype "bidirectional"))
      (node (ref "U1") (pin "38") (pinfunction "VSS_38") (pintype "power_in"))
      (node (ref "U1") (pin "51") (pinfunction "VSS_51") (pintype "power_in"))
      (node (ref "U1") (pin "61") (pinfunction "VSS_61") (pintype "power_in"))
      (node (ref "U1") (pin "83") (pinfunction "VSS_83") (pintype "power_in"))
      (node (ref "U1") (pin "94") (pinfunction "VSS_94") (pintype "power_in"))
      (node (ref "U2") (pin "15") (pinfunction "GND2_15") (pintype "power_in"))
      (node (ref "U2") (pin "9") (pinfunction "GND2_9") (pintype "power_in"))
      (node (ref "X1") (pin "11") (pinfunction "11_11") (pintype "passive"))
      (node (ref "X2") (pin "3") (pinfunction "3_3") (pintype "passive"))
      (node (ref "X3") (pin "1") (pinfunction "1_1") (pintype "passive"))
      (node (ref "X3") (pin "7") (pinfunction "7_7") (pintype "passive"))
    )
    (net (code "155") (name "Net-(D1-K)") (class "Default")
      (node (ref "D1") (pin "2") (pinfunction "K_2") (pintype "passive"))
      (node (ref "R11") (pin "2") (pinfunction "2_2") (pintype "passive"))
    )
    (net (code "156") (name "Net-(D2-K)") (class "Default")
      (node (ref "D2") (pin "2") (pinfunction "K_2") (pintype "passive"))
      (node (ref "R17") (pin "2") (pinfunction "2_2") (pintype "passive"))
    )
    (net (code "157") (name "Net-(D3-K)") (class "Default")
      (node (ref "D3") (pin "2") (pinfunction "K_2") (pintype "passive"))
      (node (ref "R20") (pin "2") (pinfunction "2_2") (pintype "passive"))
    )
    (net (code "158") (name "Net-(D4-K)") (class "Default")
      (node (ref "D4") (pin "2") (pinfunction "K_2") (pintype "passive"))
      (node (ref "R56") (pin "2") (pinfunction "2_2") (pintype "passive"))
    )
    (net (code "159") (name "Net-(D5-K)") (class "Default")
      (node (ref "D5") (pin "2") (pinfunction "K_2") (pintype "passive"))
      (node (ref "R57") (pin "2") (pinfunction "2_2") (pintype "passive"))
    )
    (net (code "160") (name "Net-(L1-Pad1)") (class "Default")
      (node (ref "L1") (pin "1") (pinfunction "1_1") (pintype "passive"))
      (node (ref "R39") (pin "1") (pinfunction "1_1") (pintype "passive"))
    )
    (net (code "161") (name "Net-(L1-Pad4)") (class "Default")
      (node (ref "L1") (pin "4") (pinfunction "4_4") (pintype "passive"))
      (node (ref "R45") (pin "1") (pinfunction "1_1") (pintype "passive"))
    )
    (net (code "162") (name "Net-(R22-Pad1)") (class "Default")
      (node (ref "R22") (pin "1") (pinfunction "1_1") (pintype "passive"))
      (node (ref "R28") (pin "1") (pinfunction "1_1") (pintype "passive"))
      (node (ref "X3") (pin "4") (pinfunction "4_4") (pintype "passive"))
    )
    (net (code "163") (name "Net-(R24-Pad1)") (class "Default")
      (node (ref "R24") (pin "1") (pinfunction "1_1") (pintype "passive"))
      (node (ref "R27") (pin "1") (pinfunction "1_1") (pintype "passive"))
      (node (ref "X3") (pin "2") (pinfunction "2_2") (pintype "passive"))
    )
    (net (code "164") (name "Net-(R30-Pad1)") (class "Default")
      (node (ref "R30") (pin "1") (pinfunction "1_1") (pintype "passive"))
      (node (ref "X3") (pin "6") (pinfunction "6_6") (pintype "passive"))
    )
    (net (code "165") (name "Net-(R32-Pad1)") (class "Default")
      (node (ref "R32") (pin "1") (pinfunction "1_1") (pintype "passive"))
      (node (ref "X3") (pin "8") (pinfunction "8_8") (pintype "passive"))
    )
    (net (code "166") (name "Net-(U1A-PA9)") (class "Default")
      (node (ref "R2") (pin "2") (pinfunction "2_2") (pintype "passive"))
      (node (ref "U1") (pin "101") (pinfunction "PA9_101") (pintype "bidirectional"))
    )
    (net (code "167") (name "Net-(U1A-PA10)") (class "Default")
      (node (ref "R4") (pin "2") (pinfunction "2_2") (pintype "passive"))
      (node (ref "U1") (pin "102") (pinfunction "PA10_102") (pintype "bidirectional"))
    )
    (net (code "168") (name "Net-(U1A-PB13)") (class "Default")
      (node (ref "R6") (pin "1") (pinfunction "1_1") (pintype "passive"))
      (node (ref "U1") (pin "74") (pinfunction "PB13_74") (pintype "bidirectional"))
    )
    (net (code "169") (name "Net-(U1A-PB14)") (class "Default")
      (node (ref "R7") (pin "1") (pinfunction "1_1") (pintype "passive"))
      (node (ref "U1") (pin "75") (pinfunction "PB14_75") (pintype "bidirectional"))
    )
    (net (code "170") (name "Net-(U1A-PB15)") (class "Default")
      (node (ref "R8") (pin "1") (pinfunction "1_1") (pintype "passive"))
      (node (ref "U1") (pin "76") (pinfunction "PB15_76") (pintype "bidirectional"))
    )
    (net (code "171") (name "Net-(U1A-PC0)") (class "Default")
      (node (ref "R10") (pin "2") (pinfunction "2_2") (pintype "passive"))
      (node (ref "U1") (pin "26") (pinfunction "PC0_26") (pintype "bidirectional"))
    )
    (net (code "172") (name "Net-(U1A-PC1)") (class "Default")
      (node (ref "R12") (pin "2") (pinfunction "2_2") (pintype "passive"))
      (node (ref "U1") (pin "27") (pinfunction "PC1_27") (pintype "bidirectional"))
    )
    (net (code "173") (name "Net-(U1A-PC2)") (class "Default")
      (node (ref "R13") (pin "2") (pinfunction "2_2") (pintype "passive"))
      (node (ref "U1") (pin "28") (pinfunction "PC2_28") (pintype "bidirectional"))
    )
    (net (code "174") (name "Net-(U1A-PC3)") (class "Default")
      (node (ref "R14") (pin "2") (pinfunction "2_2") (pintype "passive"))
      (node (ref "U1") (pin "29") (pinfunction "PC3_29") (pintype "bidirectional"))
    )
    (net (code "175") (name "Net-(U1A-PC4)") (class "Default")
      (node (ref "R15") (pin "2") (pinfunction "2_2") (pintype "passive"))
      (node (ref "U1") (pin "44") (pinfunction "PC4_44") (pintype "bidirectional"))
    )
    (net (code "176") (name "Net-(U1A-PC5)") (class "Default")
      (node (ref "R16") (pin "2") (pinfunction "2_2") (pintype "passive"))
      (node (ref "U1") (pin "45") (pinfunction "PC5_45") (pintype "bidirectional"))
    )
    (net (code "177") (name "Net-(U1A-PC6)") (class "Default")
      (node (ref "R18") (pin "2") (pinfunction "2_2") (pintype "passive"))
      (node (ref "U1") (pin "96") (pinfunction "PC6_96") (pintype "bidirectional"))
    )
    (net (code "178") (name "Net-(U1A-PC7)") (class "Default")
      (node (ref "R19") (pin "2") (pinfunction "2_2") (pintype "passive"))
      (node (ref "U1") (pin "97") (pinfunction "PC7_97") (pintype "bidirectional"))
    )
    (net (code "179") (name "Net-(U1A-PD12)") (class "Default")
      (node (ref "R21") (pin "2") (pinfunction "2_2") (pintype "passive"))
      (node (ref "U1") (pin "81") (pinfunction "PD12_81") (pintype "bidirectional"))
    )
    (net (code "180") (name "Net-(U1A-PD13)") (class "Default")
      (node (ref "R23") (pin "2") (pinfunction "2_2") (pintype "passive"))
      (node (ref "U1") (pin "82") (pinfunction "PD13_82") (pintype "bidirectional"))
    )
    (net (code "181") (name "Net-(U1A-PD14)") (class "Default")
      (node (ref "R25") (pin "2") (pinfunction "2_2") (pintype "passive"))
      (node (ref "U1") (pin "85") (pinfunction "PD14_85") (pintype "bidirectional"))
    )
    (net (code "182") (name "Net-(U1A-PD15)") (class "Default")
      (node (ref "R26") (pin "2") (pinfunction "2_2") (pintype "passive"))
      (node (ref "U1") (pin "86") (pinfunction "PD15_86") (pintype "bidirectional"))
    )
    (net (code "183") (name "Net-(U1B-BOOT0)") (class "Default")
      (node (ref "R53") (pin "2") (pinfunction "2_2") (pintype "passive"))
      (node (ref "U1") (pin "138") (pinfunction "BOOT0_138") (pintype "input"))
    )
    (net (code "184") (name "Net-(U1B-PDR_ON)") (class "Default")
      (node (ref "R54") (pin "2") (pinfunction "2_2") (pintype "passive"))
      (node (ref "U1") (pin "143") (pinfunction "PDR_ON_143") (pintype "input"))
    )
    (net (code "185") (name "Net-(U1B-PE0)") (class "Default")
      (node (ref "R33") (pin "1") (pinfunction "1_1") (pintype "passive"))
      (node (ref "U1") (pin "141") (pinfunction "PE0_141") (pintype "bidirectional"))
    )
    (net (code "186") (name "Net-(U1B-PE1)") (class "Default")
      (node (ref "R34") (pin "1") (pinfunction "1_1") (pintype "passive"))
      (node (ref "U1") (pin "142") (pinfunction "PE1_142") (pintype "bidirectional"))
    )
    (net (code "187") (name "Net-(U1B-PE2)") (class "Default")
      (node (ref "R35") (pin "1") (pinfunction "1_1") (pintype "passive"))
      (node (ref "U1") (pin "1") (pinfunction "PE2_1") (pintype "bidirectional"))
    )
    (net (code "188") (name "Net-(U1B-PE3)") (class "Default")
      (node (ref "R37") (pin "1") (pinfunction "1_1") (pintype "passive"))
      (node (ref "U1") (pin "2") (pinfunction "PE3_2") (pintype "bidirectional"))
    )
    (net (code "189") (name "Net-(U1B-PE4)") (class "Default")
      (node (ref "R41") (pin "1") (pinfunction "1_1") (pintype "passive"))
      (node (ref "U1") (pin "3") (pinfunction "PE4_3") (pintype "bidirectional"))
    )
    (net (code "190") (name "Net-(U1B-PE5)") (class "Default")
      (node (ref "R43") (pin "1") (pinfunction "1_1") (pintype "passive"))
      (node (ref "U1") (pin "4") (pinfunction "PE5_4") (pintype "bidirectional"))
    )
    (net (code "191") (name "Net-(U1B-PE6)") (class "Default")
      (node (ref "R47") (pin "1") (pinfunction "1_1") (pintype "passive"))
      (node (ref "U1") (pin "5") (pinfunction "PE6_5") (pintype "bidirectional"))
    )
    (net (code "192") (name "Net-(U1B-PF2)") (class "Default")
      (node (ref "R36") (pin "2") (pinfunction "2_2") (pintype "passive"))
      (node (ref "U1") (pin "12") (pinfunction "PF2_12") (pintype "bidirectional"))
    )
    (net (code "193") (name "Net-(U1B-PF3)") (class "Default")
      (node (ref "R38") (pin "2") (pinfunction "2_2") (pintype "passive"))
      (node (ref "U1") (pin "13") (pinfunction "PF3_13") (pintype "bidirectional"))
    )
    (net (code "194") (name "Net-(U1B-PF4)") (class "Default")
      (node (ref "R42") (pin "2") (pinfunction "2_2") (pintype "passive"))
      (node (ref "U1") (pin "14") (pinfunction "PF4_14") (pintype "bidirectional"))
    )
    (net (code "195") (name "Net-(U1B-PF5)") (class "Default")
      (node (ref "R44") (pin "2") (pinfunction "2_2") (pintype "passive"))
      (node (ref "U1") (pin "15") (pinfunction "PF5_15") (pintype "bidirectional"))
    )
    (net (code "196") (name "Net-(U1B-PH0-OSC_IN(PH0))") (class "Default")
      (node (ref "R48") (pin "2") (pinfunction "2_2") (pintype "passive"))
      (node (ref "U1") (pin "23") (pinfunction "PH0-OSC_IN(PH0)_23") (pintype "bidirectional"))
    )
    (net (code "197") (name "Net-(U1B-VCAP_1)") (class "Default")
      (node (ref "C21") (pin "2") (pinfunction "2_2") (pintype "passive"))
      (node (ref "U1") (pin "71") (pinfunction "VCAP_1_71") (pintype "power_in"))
    )
    (net (code "198") (name "Net-(U1B-VCAP_2)") (class "Default")
      (node (ref "C20") (pin "2") (pinfunction "2_2") (pintype "passive"))
      (node (ref "U1") (pin "106") (pinfunction "VCAP_2_106") (pintype "power_in"))
    )
    (net (code "199") (name "Net-(U2-PDEN)") (class "Default")
      (node (ref "C5") (pin "2") (pinfunction "2_2") (pintype "passive"))
      (node (ref "U2") (pin "3") (pinfunction "VDD1_3") (pintype "power_in"))
      (node (ref "U2") (pin "4") (pinfunction "PDEN_4") (pintype "input"))
      (node (ref "U2") (pin "5") (pinfunction "SPU_5") (pintype "input"))
    )
    (net (code "200") (name "Net-(X4-GND)") (class "Default")
      (node (ref "L2") (pin "2") (pinfunction "2_2") (pintype "passive"))
      (node (ref "X4") (pin "4") (pinfunction "GND_4") (pintype "power_in"))
    )
    (net (code "201") (name "PC_GND") (class "Default")
      (node (ref "C3") (pin "2") (pinfunction "2_2") (pintype "passive"))
      (node (ref "C4") (pin "2") (pinfunction "2_2") (pintype "passive"))
      (node (ref "C5") (pin "1") (pinfunction "1_1") (pintype "passive"))
      (node (ref "C7") (pin "1") (pinfunction "1_1") (pintype "passive"))
      (node (ref "L2") (pin "1") (pinfunction "1_1") (pintype "passive"))
      (node (ref "R49") (pin "1") (pinfunction "1_1") (pintype "passive"))
      (node (ref "R50") (pin "1") (pinfunction "1_1") (pintype "passive"))
      (node (ref "U2") (pin "2") (pinfunction "GND1_2") (pintype "power_in"))
      (node (ref "U2") (pin "8") (pinfunction "GND1_8") (pintype "power_in"))
      (node (ref "X4") (pin "S1") (pinfunction "Shield1_S1") (pintype "power_in"))
      (node (ref "X4") (pin "S2") (pinfunction "Shield2_S2") (pintype "power_in"))
    )
    (net (code "202") (name "VRef") (class "Default")
      (node (ref "U1") (pin "32") (pinfunction "VREF+_32") (pintype "power_in"))
    )
    (net (code "203") (name "unconnected-(U1A-PA4-Pad40)") (class "Default")
      (node (ref "U1") (pin "40") (pinfunction "PA4_40") (pintype "bidirectional"))
    )
    (net (code "204") (name "unconnected-(U1A-PA5-Pad41)") (class "Default")
      (node (ref "U1") (pin "41") (pinfunction "PA5_41") (pintype "bidirectional"))
    )
    (net (code "205") (name "unconnected-(U1A-PA6-Pad42)") (class "Default")
      (node (ref "U1") (pin "42") (pinfunction "PA6_42") (pintype "bidirectional"))
    )
    (net (code "206") (name "unconnected-(U1A-PA7-Pad43)") (class "Default")
      (node (ref "U1") (pin "43") (pinfunction "PA7_43") (pintype "bidirectional"))
    )
    (net (code "207") (name "unconnected-(U1A-PA8-Pad100)") (class "Default")
      (node (ref "U1") (pin "100") (pinfunction "PA8_100") (pintype "bidirectional"))
    )
    (net (code "208") (name "unconnected-(U1A-PB0-Pad46)") (class "Default")
      (node (ref "U1") (pin "46") (pinfunction "PB0_46") (pintype "bidirectional"))
    )
    (net (code "209") (name "unconnected-(U1A-PB1-Pad47)") (class "Default")
      (node (ref "U1") (pin "47") (pinfunction "PB1_47") (pintype "bidirectional"))
    )
    (net (code "210") (name "unconnected-(U1A-PB2-BOOT1(PB2)-Pad48)") (class "Default")
      (node (ref "U1") (pin "48") (pinfunction "PB2-BOOT1(PB2)_48") (pintype "bidirectional"))
    )
    (net (code "211") (name "unconnected-(U1A-PB4(NJTRST)-Pad134)") (class "Default")
      (node (ref "U1") (pin "134") (pinfunction "PB4(NJTRST)_134") (pintype "bidirectional"))
    )
    (net (code "212") (name "unconnected-(U1A-PB5-Pad135)") (class "Default")
      (node (ref "U1") (pin "135") (pinfunction "PB5_135") (pintype "bidirectional"))
    )
    (net (code "213") (name "unconnected-(U1A-PB8-Pad139)") (class "Default")
      (node (ref "U1") (pin "139") (pinfunction "PB8_139") (pintype "bidirectional"))
    )
    (net (code "214") (name "unconnected-(U1A-PB9-Pad140)") (class "Default")
      (node (ref "U1") (pin "140") (pinfunction "PB9_140") (pintype "bidirectional"))
    )
    (net (code "215") (name "unconnected-(U1A-PB10-Pad69)") (class "Default")
      (node (ref "U1") (pin "69") (pinfunction "PB10_69") (pintype "bidirectional"))
    )
    (net (code "216") (name "unconnected-(U1A-PB11-Pad70)") (class "Default")
      (node (ref "U1") (pin "70") (pinfunction "PB11_70") (pintype "bidirectional"))
    )
    (net (code "217") (name "unconnected-(U1A-PB12-Pad73)") (class "Default")
      (node (ref "U1") (pin "73") (pinfunction "PB12_73") (pintype "bidirectional"))
    )
    (net (code "218") (name "unconnected-(U1A-PC8-Pad98)") (class "Default")
      (node (ref "U1") (pin "98") (pinfunction "PC8_98") (pintype "bidirectional"))
    )
    (net (code "219") (name "unconnected-(U1A-PC9-Pad99)") (class "Default")
      (node (ref "U1") (pin "99") (pinfunction "PC9_99") (pintype "bidirectional"))
    )
    (net (code "220") (name "unconnected-(U1A-PC10-Pad111)") (class "Default")
      (node (ref "U1") (pin "111") (pinfunction "PC10_111") (pintype "bidirectional"))
    )
    (net (code "221") (name "unconnected-(U1A-PC11-Pad112)") (class "Default")
      (node (ref "U1") (pin "112") (pinfunction "PC11_112") (pintype "bidirectional"))
    )
    (net (code "222") (name "unconnected-(U1A-PC12-Pad113)") (class "Default")
      (node (ref "U1") (pin "113") (pinfunction "PC12_113") (pintype "bidirectional"))
    )
    (net (code "223") (name "unconnected-(U1A-PC14-OSC32_IN(PC14)-Pad8)") (class "Default")
      (node (ref "U1") (pin "8") (pinfunction "PC14-OSC32_IN(PC14)_8") (pintype "bidirectional"))
    )
    (net (code "224") (name "unconnected-(U1A-PC15-OSC32_OUT(PC15)-Pad9)") (class "Default")
      (node (ref "U1") (pin "9") (pinfunction "PC15-OSC32_OUT(PC15)_9") (pintype "bidirectional"))
    )
    (net (code "225") (name "unconnected-(U1A-PD0-Pad114)") (class "Default")
      (node (ref "U1") (pin "114") (pinfunction "PD0_114") (pintype "bidirectional"))
    )
    (net (code "226") (name "unconnected-(U1A-PD1-Pad115)") (class "Default")
      (node (ref "U1") (pin "115") (pinfunction "PD1_115") (pintype "bidirectional"))
    )
    (net (code "227") (name "unconnected-(U1A-PD2-Pad116)") (class "Default")
      (node (ref "U1") (pin "116") (pinfunction "PD2_116") (pintype "bidirectional"))
    )
    (net (code "228") (name "unconnected-(U1A-PD5-Pad119)") (class "Default")
      (node (ref "U1") (pin "119") (pinfunction "PD5_119") (pintype "bidirectional"))
    )
    (net (code "229") (name "unconnected-(U1A-PD6-Pad122)") (class "Default")
      (node (ref "U1") (pin "122") (pinfunction "PD6_122") (pintype "bidirectional"))
    )
    (net (code "230") (name "unconnected-(U1A-PD7-Pad123)") (class "Default")
      (node (ref "U1") (pin "123") (pinfunction "PD7_123") (pintype "bidirectional"))
    )
    (net (code "231") (name "unconnected-(U1A-PD8-Pad77)") (class "Default")
      (node (ref "U1") (pin "77") (pinfunction "PD8_77") (pintype "bidirectional"))
    )
    (net (code "232") (name "unconnected-(U1A-PD9-Pad78)") (class "Default")
      (node (ref "U1") (pin "78") (pinfunction "PD9_78") (pintype "bidirectional"))
    )
    (net (code "233") (name "unconnected-(U1A-PD10-Pad79)") (class "Default")
      (node (ref "U1") (pin "79") (pinfunction "PD10_79") (pintype "bidirectional"))
    )
    (net (code "234") (name "unconnected-(U1A-PD11-Pad80)") (class "Default")
      (node (ref "U1") (pin "80") (pinfunction "PD11_80") (pintype "bidirectional"))
    )
    (net (code "235") (name "unconnected-(U1B-PE7-Pad58)") (class "Default")
      (node (ref "U1") (pin "58") (pinfunction "PE7_58") (pintype "bidirectional"))
    )
    (net (code "236") (name "unconnected-(U1B-PE8-Pad59)") (class "Default")
      (node (ref "U1") (pin "59") (pinfunction "PE8_59") (pintype "bidirectional"))
    )
    (net (code "237") (name "unconnected-(U1B-PE9-Pad60)") (class "Default")
      (node (ref "U1") (pin "60") (pinfunction "PE9_60") (pintype "bidirectional"))
    )
    (net (code "238") (name "unconnected-(U1B-PE10-Pad63)") (class "Default")
      (node (ref "U1") (pin "63") (pinfunction "PE10_63") (pintype "bidirectional"))
    )
    (net (code "239") (name "unconnected-(U1B-PE11-Pad64)") (class "Default")
      (node (ref "U1") (pin "64") (pinfunction "PE11_64") (pintype "bidirectional"))
    )
    (net (code "240") (name "unconnected-(U1B-PE12-Pad65)") (class "Default")
      (node (ref "U1") (pin "65") (pinfunction "PE12_65") (pintype "bidirectional"))
    )
    (net (code "241") (name "unconnected-(U1B-PE13-Pad66)") (class "Default")
      (node (ref "U1") (pin "66") (pinfunction "PE13_66") (pintype "bidirectional"))
    )
    (net (code "242") (name "unconnected-(U1B-PE14-Pad67)") (class "Default")
      (node (ref "U1") (pin "67") (pinfunction "PE14_67") (pintype "bidirectional"))
    )
    (net (code "243") (name "unconnected-(U1B-PE15-Pad68)") (class "Default")
      (node (ref "U1") (pin "68") (pinfunction "PE15_68") (pintype "bidirectional"))
    )
    (net (code "244") (name "unconnected-(U1B-PF6-Pad18)") (class "Default")
      (node (ref "U1") (pin "18") (pinfunction "PF6_18") (pintype "bidirectional"))
    )
    (net (code "245") (name "unconnected-(U1B-PF7-Pad19)") (class "Default")
      (node (ref "U1") (pin "19") (pinfunction "PF7_19") (pintype "bidirectional"))
    )
    (net (code "246") (name "unconnected-(U1B-PF8-Pad20)") (class "Default")
      (node (ref "U1") (pin "20") (pinfunction "PF8_20") (pintype "bidirectional"))
    )
    (net (code "247") (name "unconnected-(U1B-PF9-Pad21)") (class "Default")
      (node (ref "U1") (pin "21") (pinfunction "PF9_21") (pintype "bidirectional"))
    )
    (net (code "248") (name "unconnected-(U1B-PF10-Pad22)") (class "Default")
      (node (ref "U1") (pin "22") (pinfunction "PF10_22") (pintype "bidirectional"))
    )
    (net (code "249") (name "unconnected-(U1B-PF11-Pad49)") (class "Default")
      (node (ref "U1") (pin "49") (pinfunction "PF11_49") (pintype "bidirectional"))
    )
    (net (code "250") (name "unconnected-(U1B-PF12-Pad50)") (class "Default")
      (node (ref "U1") (pin "50") (pinfunction "PF12_50") (pintype "bidirectional"))
    )
    (net (code "251") (name "unconnected-(U1B-PF13-Pad53)") (class "Default")
      (node (ref "U1") (pin "53") (pinfunction "PF13_53") (pintype "bidirectional"))
    )
    (net (code "252") (name "unconnected-(U1B-PF14-Pad54)") (class "Default")
      (node (ref "U1") (pin "54") (pinfunction "PF14_54") (pintype "bidirectional"))
    )
    (net (code "253") (name "unconnected-(U1B-PF15-Pad55)") (class "Default")
      (node (ref "U1") (pin "55") (pinfunction "PF15_55") (pintype "bidirectional"))
    )
    (net (code "254") (name "unconnected-(U1B-PG0-Pad56)") (class "Default")
      (node (ref "U1") (pin "56") (pinfunction "PG0_56") (pintype "bidirectional"))
    )
    (net (code "255") (name "unconnected-(U1B-PG1-Pad57)") (class "Default")
      (node (ref "U1") (pin "57") (pinfunction "PG1_57") (pintype "bidirectional"))
    )
    (net (code "256") (name "unconnected-(U1B-PG2-Pad87)") (class "Default")
      (node (ref "U1") (pin "87") (pinfunction "PG2_87") (pintype "bidirectional"))
    )
    (net (code "257") (name "unconnected-(U1B-PG3-Pad88)") (class "Default")
      (node (ref "U1") (pin "88") (pinfunction "PG3_88") (pintype "bidirectional"))
    )
    (net (code "258") (name "unconnected-(U1B-PG4-Pad89)") (class "Default")
      (node (ref "U1") (pin "89") (pinfunction "PG4_89") (pintype "bidirectional"))
    )
    (net (code "259") (name "unconnected-(U1B-PG5-Pad90)") (class "Default")
      (node (ref "U1") (pin "90") (pinfunction "PG5_90") (pintype "bidirectional"))
    )
    (net (code "260") (name "unconnected-(U1B-PG6-Pad91)") (class "Default")
      (node (ref "U1") (pin "91") (pinfunction "PG6_91") (pintype "bidirectional"))
    )
    (net (code "261") (name "unconnected-(U1B-PG7-Pad92)") (class "Default")
      (node (ref "U1") (pin "92") (pinfunction "PG7_92") (pintype "bidirectional"))
    )
    (net (code "262") (name "unconnected-(U1B-PG8-Pad93)") (class "Default")
      (node (ref "U1") (pin "93") (pinfunction "PG8_93") (pintype "bidirectional"))
    )
    (net (code "263") (name "unconnected-(U1B-PG9-Pad124)") (class "Default")
      (node (ref "U1") (pin "124") (pinfunction "PG9_124") (pintype "bidirectional"))
    )
    (net (code "264") (name "unconnected-(U1B-PG10-Pad125)") (class "Default")
      (node (ref "U1") (pin "125") (pinfunction "PG10_125") (pintype "bidirectional"))
    )
    (net (code "265") (name "unconnected-(U1B-PG11-Pad126)") (class "Default")
      (node (ref "U1") (pin "126") (pinfunction "PG11_126") (pintype "bidirectional"))
    )
    (net (code "266") (name "unconnected-(U1B-PG12-Pad127)") (class "Default")
      (node (ref "U1") (pin "127") (pinfunction "PG12_127") (pintype "bidirectional"))
    )
    (net (code "267") (name "unconnected-(U1B-PG13-Pad128)") (class "Default")
      (node (ref "U1") (pin "128") (pinfunction "PG13_128") (pintype "bidirectional"))
    )
    (net (code "268") (name "unconnected-(U1B-PG14-Pad129)") (class "Default")
      (node (ref "U1") (pin "129") (pinfunction "PG14_129") (pintype "bidirectional"))
    )
    (net (code "269") (name "unconnected-(U1B-PG15-Pad132)") (class "Default")
      (node (ref "U1") (pin "132") (pinfunction "PG15_132") (pintype "bidirectional"))
    )
    (net (code "270") (name "unconnected-(U3-A-Pad8)") (class "Default")
      (node (ref "U3") (pin "8") (pinfunction "A_8") (pintype "bidirectional"))
    )
    (net (code "271") (name "unconnected-(U3-C-Pad2)") (class "Default")
      (node (ref "U3") (pin "2") (pinfunction "C_2") (pintype "bidirectional"))
    )
    (net (code "272") (name "unconnected-(U3-D-Pad4)") (class "Default")
      (node (ref "U3") (pin "4") (pinfunction "D_4") (pintype "bidirectional"))
    )
    (net (code "273") (name "unconnected-(U3-GND-Pad1)") (class "Default")
      (node (ref "U3") (pin "1") (pinfunction "GND_1") (pintype "power_in"))
    )
    (net (code "274") (name "unconnected-(U3-GND-Pad3)") (class "Default")
      (node (ref "U3") (pin "3") (pinfunction "GND_3") (pintype "power_in"))
    )
    (net (code "275") (name "unconnected-(U3-GND-Pad7)") (class "Default")
      (node (ref "U3") (pin "7") (pinfunction "GND_7") (pintype "power_in"))
    )
  )
)
